# sprint_logger.net
KiCad netlist of a schematic drawn in EAGLE
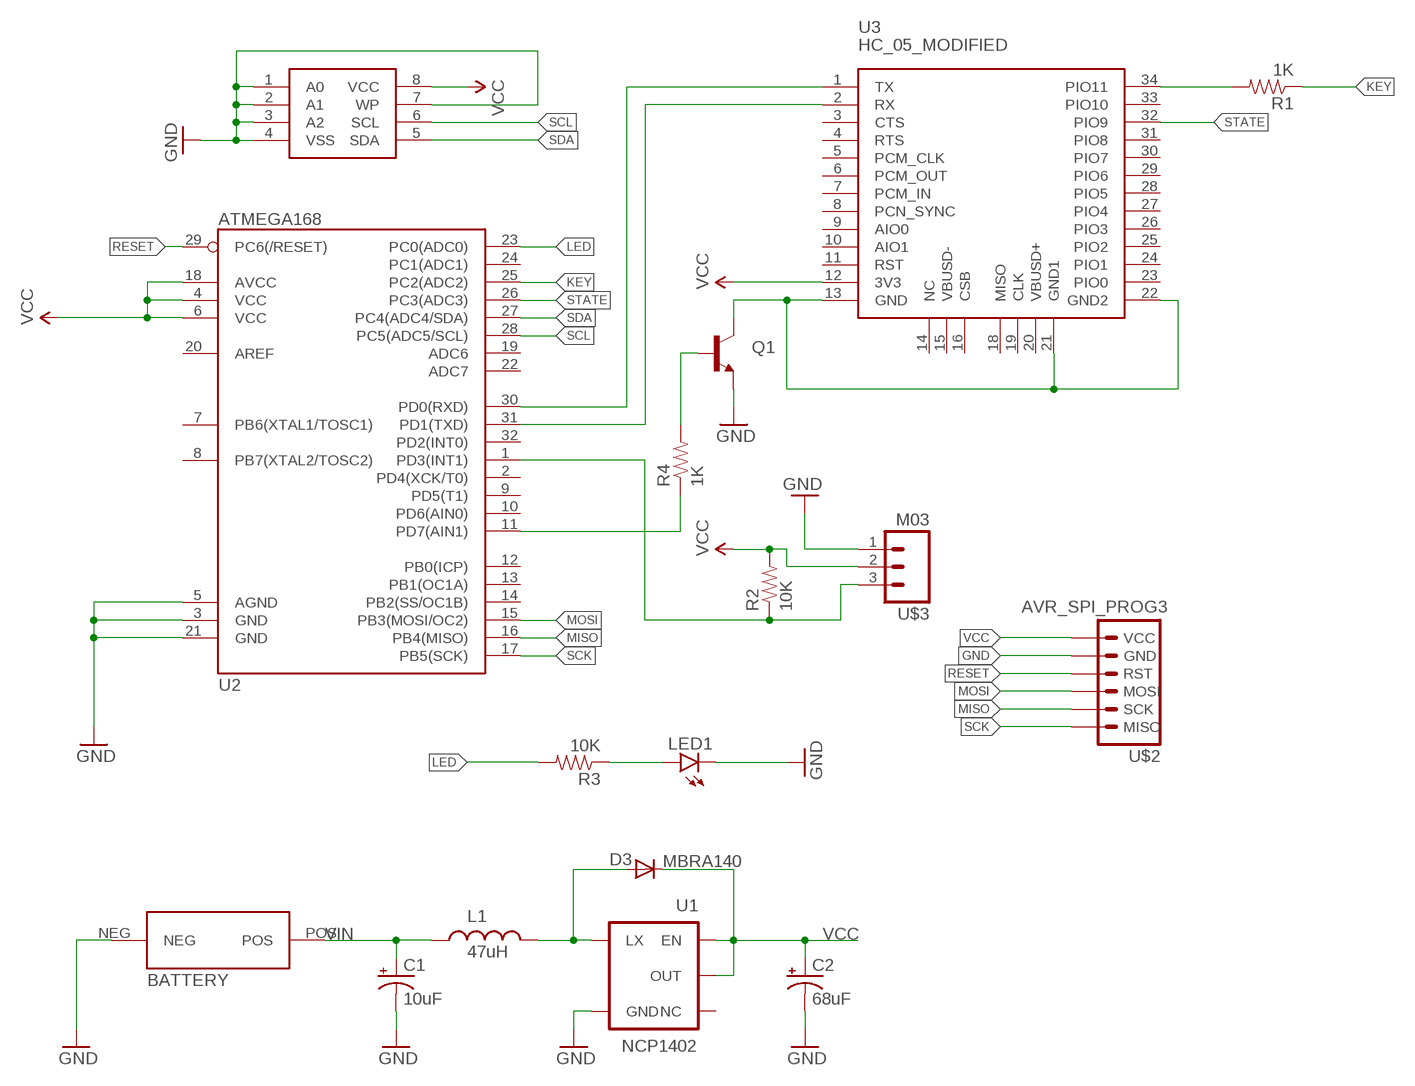
[diagram p0: schematic, sheet 1]

(export (version "E")
  (design (tool "Eeschema 10.0.6"))
  (components
    (comp (ref "BATTERY")
      (value "BATHOLDER-N-2470")
      (footprint "eagle-import:BATHOLDER-N-2470")
      (libsource (lib "eagle-import") (part "BATHOLDER-N-2470"))
    )
    (comp (ref "C1")
      (value "10uF")
      (footprint "eagle-import:EIA3216")
      (libsource (lib "eagle-import") (part "CAP_POL1206"))
    )
    (comp (ref "C2")
      (value "68uF")
      (footprint "eagle-import:EIA3528")
      (libsource (lib "eagle-import") (part "CAP_POL3528"))
    )
    (comp (ref "D3")
      (value "MBRA140")
      (footprint "eagle-import:SMA-DIODE")
      (libsource (lib "eagle-import") (part "DIODESMA"))
    )
    (comp (ref "L1")
      (value "47uH")
      (footprint "eagle-import:CR54")
      (libsource (lib "eagle-import") (part "INDUCTORCR54"))
    )
    (comp (ref "LED1")
      (value "LED1206")
      (footprint "eagle-import:LED-1206")
      (libsource (lib "eagle-import") (part "LED1206"))
    )
    (comp (ref "Q1")
      (value "TRANSISTOR_NPNSOT23")
      (footprint "eagle-import:SOT23")
      (libsource (lib "eagle-import") (part "TRANSISTOR_NPNSOT23"))
    )
    (comp (ref "R1")
      (value "1K")
      (footprint "eagle-import:0805")
      (libsource (lib "eagle-import") (part "RESISTOR0805-RES"))
    )
    (comp (ref "R2")
      (value "10K")
      (footprint "eagle-import:0805")
      (libsource (lib "eagle-import") (part "RESISTOR0805-RES"))
    )
    (comp (ref "R3")
      (value "10K")
      (footprint "eagle-import:0805")
      (libsource (lib "eagle-import") (part "RESISTOR0805-RES"))
    )
    (comp (ref "R4")
      (value "1K")
      (footprint "eagle-import:0805")
      (libsource (lib "eagle-import") (part "RESISTOR0805-RES"))
    )
    (comp (ref "U$1")
      (value "24AAXXX")
      (footprint "eagle-import:SOIC-8-EIAJ")
      (libsource (lib "eagle-import") (part "24AAXXX"))
    )
    (comp (ref "U$2")
      (value "AVR_SPI_PROG3")
      (footprint "eagle-import:1X06-SMD_EDGE")
      (libsource (lib "eagle-import") (part "AVR_SPI_PROG3"))
    )
    (comp (ref "U$3")
      (value "M03")
      (footprint "eagle-import:1X06-SMD_EDGE")
      (libsource (lib "eagle-import") (part "M03"))
    )
    (comp (ref "U1")
      (value "NCP1402")
      (footprint "eagle-import:SOT23-5")
      (libsource (lib "eagle-import") (part "V_REG_NCP1400SOT23-5"))
    )
    (comp (ref "U2")
      (value "ATMEGA168")
      (footprint "eagle-import:TQFP32-08")
      (libsource (lib "eagle-import") (part "ATMEGA168"))
    )
    (comp (ref "U3")
      (value "HC_05_MODIFIED")
      (footprint "eagle-import:BLUETOOTH_SMD_MODIFIED")
      (libsource (lib "eagle-import") (part "HC_05_MODIFIED"))
    )
  )
  (nets
    (net (code "1") (name "/VIN") (class "Default")
      (node (ref "BATTERY") (pin "POS") (pinfunction "POS_POS") (pintype "bidirectional"))
      (node (ref "C1") (pin "A") (pinfunction "+_A") (pintype "passive"))
      (node (ref "L1") (pin "P$1") (pinfunction "1_P$1") (pintype "passive"))
    )
    (net (code "2") (name "GND") (class "Default")
      (node (ref "BATTERY") (pin "NEG") (pinfunction "NEG_NEG") (pintype "bidirectional"))
      (node (ref "C1") (pin "C") (pinfunction "-_C") (pintype "passive"))
      (node (ref "C2") (pin "C") (pinfunction "-_C") (pintype "passive"))
      (node (ref "LED1") (pin "C") (pinfunction "C_C") (pintype "passive"))
      (node (ref "Q1") (pin "2") (pinfunction "E_2") (pintype "passive"))
      (node (ref "U$1") (pin "1") (pinfunction "A0_1") (pintype "bidirectional"))
      (node (ref "U$1") (pin "2") (pinfunction "A1_2") (pintype "bidirectional"))
      (node (ref "U$1") (pin "3") (pinfunction "A2_3") (pintype "bidirectional"))
      (node (ref "U$1") (pin "4") (pinfunction "VSS_4") (pintype "bidirectional"))
      (node (ref "U$1") (pin "7") (pinfunction "WP_7") (pintype "bidirectional"))
      (node (ref "U$2") (pin "2") (pinfunction "GND_2") (pintype "passive"))
      (node (ref "U$3") (pin "1") (pinfunction "1_1") (pintype "passive"))
      (node (ref "U1") (pin "4") (pinfunction "GND_4") (pintype "input"))
      (node (ref "U2") (pin "21") (pinfunction "GND_21") (pintype "bidirectional"))
      (node (ref "U2") (pin "3") (pinfunction "GND_3") (pintype "bidirectional"))
      (node (ref "U2") (pin "5") (pinfunction "AGND_5") (pintype "bidirectional"))
    )
    (net (code "3") (name "KEY") (class "Default")
      (node (ref "R1") (pin "1") (pinfunction "1_1") (pintype "passive"))
      (node (ref "U2") (pin "25") (pinfunction "PC2(ADC2)_25") (pintype "bidirectional"))
    )
    (net (code "4") (name "LED") (class "Default")
      (node (ref "R3") (pin "2") (pinfunction "2_2") (pintype "passive"))
      (node (ref "U2") (pin "23") (pinfunction "PC0(ADC0)_23") (pintype "bidirectional"))
    )
    (net (code "5") (name "MISO") (class "Default")
      (node (ref "U$2") (pin "5") (pinfunction "SCK_5") (pintype "passive"))
      (node (ref "U2") (pin "16") (pinfunction "PB4(MISO)_16") (pintype "bidirectional"))
    )
    (net (code "6") (name "MOSI") (class "Default")
      (node (ref "U$2") (pin "4") (pinfunction "MOSI_4") (pintype "passive"))
      (node (ref "U2") (pin "15") (pinfunction "PB3(MOSI/OC2)_15") (pintype "bidirectional"))
    )
    (net (code "7") (name "Net-(L1-2)") (class "Default")
      (node (ref "D3") (pin "A") (pinfunction "A_A") (pintype "passive"))
      (node (ref "L1") (pin "P$2") (pinfunction "2_P$2") (pintype "passive"))
      (node (ref "U1") (pin "5") (pinfunction "LX_5") (pintype "input"))
    )
    (net (code "8") (name "Net-(LED1-PadA)") (class "Default")
      (node (ref "LED1") (pin "A") (pinfunction "A_A") (pintype "passive"))
      (node (ref "R3") (pin "1") (pinfunction "1_1") (pintype "passive"))
    )
    (net (code "9") (name "Net-(Q1-B)") (class "Default")
      (node (ref "Q1") (pin "1") (pinfunction "B_1") (pintype "passive"))
      (node (ref "R4") (pin "2") (pinfunction "2_2") (pintype "passive"))
    )
    (net (code "10") (name "Net-(Q1-C)") (class "Default")
      (node (ref "Q1") (pin "3") (pinfunction "C_3") (pintype "passive"))
      (node (ref "U3") (pin "13") (pinfunction "GND_13") (pintype "bidirectional"))
      (node (ref "U3") (pin "21") (pinfunction "GND1_21") (pintype "bidirectional"))
      (node (ref "U3") (pin "22") (pinfunction "GND2_22") (pintype "bidirectional"))
    )
    (net (code "11") (name "Net-(U2-PD0(RXD))") (class "Default")
      (node (ref "U2") (pin "30") (pinfunction "PD0(RXD)_30") (pintype "bidirectional"))
      (node (ref "U3") (pin "1") (pinfunction "TX_1") (pintype "bidirectional"))
    )
    (net (code "12") (name "Net-(U2-PD1(TXD))") (class "Default")
      (node (ref "U2") (pin "31") (pinfunction "PD1(TXD)_31") (pintype "bidirectional"))
      (node (ref "U3") (pin "2") (pinfunction "RX_2") (pintype "bidirectional"))
    )
    (net (code "13") (name "Net-(U2-PD3(INT1))") (class "Default")
      (node (ref "R2") (pin "1") (pinfunction "1_1") (pintype "passive"))
      (node (ref "U$3") (pin "3") (pinfunction "3_3") (pintype "passive"))
      (node (ref "U2") (pin "1") (pinfunction "PD3(INT1)_1") (pintype "bidirectional"))
    )
    (net (code "14") (name "Net-(U2-PD7(AIN1))") (class "Default")
      (node (ref "R4") (pin "1") (pinfunction "1_1") (pintype "passive"))
      (node (ref "U2") (pin "11") (pinfunction "PD7(AIN1)_11") (pintype "bidirectional"))
    )
    (net (code "15") (name "Net-(U3-PIO11)") (class "Default")
      (node (ref "R1") (pin "2") (pinfunction "2_2") (pintype "passive"))
      (node (ref "U3") (pin "34") (pinfunction "PIO11_34") (pintype "bidirectional"))
    )
    (net (code "16") (name "RESET") (class "Default")
      (node (ref "U$2") (pin "3") (pinfunction "RST_3") (pintype "passive"))
      (node (ref "U2") (pin "29") (pinfunction "PC6(/RESET)_29") (pintype "bidirectional"))
    )
    (net (code "17") (name "SCK") (class "Default")
      (node (ref "U$2") (pin "6") (pinfunction "MISO_6") (pintype "passive"))
      (node (ref "U2") (pin "17") (pinfunction "PB5(SCK)_17") (pintype "bidirectional"))
    )
    (net (code "18") (name "SCL") (class "Default")
      (node (ref "U$1") (pin "6") (pinfunction "SCL_6") (pintype "bidirectional"))
      (node (ref "U2") (pin "28") (pinfunction "PC5(ADC5/SCL)_28") (pintype "bidirectional"))
    )
    (net (code "19") (name "SDA") (class "Default")
      (node (ref "U$1") (pin "5") (pinfunction "SDA_5") (pintype "bidirectional"))
      (node (ref "U2") (pin "27") (pinfunction "PC4(ADC4/SDA)_27") (pintype "bidirectional"))
    )
    (net (code "20") (name "STATE") (class "Default")
      (node (ref "U2") (pin "26") (pinfunction "PC3(ADC3)_26") (pintype "bidirectional"))
      (node (ref "U3") (pin "32") (pinfunction "PIO9_32") (pintype "bidirectional"))
    )
    (net (code "21") (name "VCC") (class "Default")
      (node (ref "C2") (pin "A") (pinfunction "+_A") (pintype "passive"))
      (node (ref "D3") (pin "C") (pinfunction "C_C") (pintype "passive"))
      (node (ref "R2") (pin "2") (pinfunction "2_2") (pintype "passive"))
      (node (ref "U$1") (pin "8") (pinfunction "VCC_8") (pintype "bidirectional"))
      (node (ref "U$2") (pin "1") (pinfunction "VCC_1") (pintype "passive"))
      (node (ref "U$3") (pin "2") (pinfunction "2_2") (pintype "passive"))
      (node (ref "U1") (pin "1") (pinfunction "EN_1") (pintype "input"))
      (node (ref "U1") (pin "2") (pinfunction "OUT_2") (pintype "passive"))
      (node (ref "U2") (pin "18") (pinfunction "AVCC_18") (pintype "bidirectional"))
      (node (ref "U2") (pin "4") (pinfunction "VCC_4") (pintype "bidirectional"))
      (node (ref "U2") (pin "6") (pinfunction "VCC_6") (pintype "bidirectional"))
      (node (ref "U3") (pin "12") (pinfunction "3V3_12") (pintype "bidirectional"))
    )
    (net (code "22") (name "unconnected-(U1-NC-Pad3)") (class "Default")
      (node (ref "U1") (pin "3") (pinfunction "NC_3") (pintype "input"))
    )
    (net (code "23") (name "unconnected-(U2-ADC6-Pad19)") (class "Default")
      (node (ref "U2") (pin "19") (pinfunction "ADC6_19") (pintype "bidirectional"))
    )
    (net (code "24") (name "unconnected-(U2-ADC7-Pad22)") (class "Default")
      (node (ref "U2") (pin "22") (pinfunction "ADC7_22") (pintype "bidirectional"))
    )
    (net (code "25") (name "unconnected-(U2-AREF-Pad20)") (class "Default")
      (node (ref "U2") (pin "20") (pinfunction "AREF_20") (pintype "bidirectional"))
    )
    (net (code "26") (name "unconnected-(U2-PB0(ICP)-Pad12)") (class "Default")
      (node (ref "U2") (pin "12") (pinfunction "PB0(ICP)_12") (pintype "bidirectional"))
    )
    (net (code "27") (name "unconnected-(U2-PB1(OC1A)-Pad13)") (class "Default")
      (node (ref "U2") (pin "13") (pinfunction "PB1(OC1A)_13") (pintype "bidirectional"))
    )
    (net (code "28") (name "unconnected-(U2-PB2(SS{slash}OC1B)-Pad14)") (class "Default")
      (node (ref "U2") (pin "14") (pinfunction "PB2(SS/OC1B)_14") (pintype "bidirectional"))
    )
    (net (code "29") (name "unconnected-(U2-PB6(XTAL1{slash}TOSC1)-Pad7)") (class "Default")
      (node (ref "U2") (pin "7") (pinfunction "PB6(XTAL1/TOSC1)_7") (pintype "bidirectional"))
    )
    (net (code "30") (name "unconnected-(U2-PB7(XTAL2{slash}TOSC2)-Pad8)") (class "Default")
      (node (ref "U2") (pin "8") (pinfunction "PB7(XTAL2/TOSC2)_8") (pintype "bidirectional"))
    )
    (net (code "31") (name "unconnected-(U2-PC1(ADC1)-Pad24)") (class "Default")
      (node (ref "U2") (pin "24") (pinfunction "PC1(ADC1)_24") (pintype "bidirectional"))
    )
    (net (code "32") (name "unconnected-(U2-PD2(INT0)-Pad32)") (class "Default")
      (node (ref "U2") (pin "32") (pinfunction "PD2(INT0)_32") (pintype "bidirectional"))
    )
    (net (code "33") (name "unconnected-(U2-PD4(XCK{slash}T0)-Pad2)") (class "Default")
      (node (ref "U2") (pin "2") (pinfunction "PD4(XCK/T0)_2") (pintype "bidirectional"))
    )
    (net (code "34") (name "unconnected-(U2-PD5(T1)-Pad9)") (class "Default")
      (node (ref "U2") (pin "9") (pinfunction "PD5(T1)_9") (pintype "bidirectional"))
    )
    (net (code "35") (name "unconnected-(U2-PD6(AIN0)-Pad10)") (class "Default")
      (node (ref "U2") (pin "10") (pinfunction "PD6(AIN0)_10") (pintype "bidirectional"))
    )
    (net (code "36") (name "unconnected-(U3-AIO0-Pad9)") (class "Default")
      (node (ref "U3") (pin "9") (pinfunction "AIO0_9") (pintype "bidirectional"))
    )
    (net (code "37") (name "unconnected-(U3-AIO1-Pad10)") (class "Default")
      (node (ref "U3") (pin "10") (pinfunction "AIO1_10") (pintype "bidirectional"))
    )
    (net (code "38") (name "unconnected-(U3-CLK-Pad19)") (class "Default")
      (node (ref "U3") (pin "19") (pinfunction "CLK_19") (pintype "bidirectional"))
    )
    (net (code "39") (name "unconnected-(U3-CSB-Pad16)") (class "Default")
      (node (ref "U3") (pin "16") (pinfunction "CSB_16") (pintype "bidirectional"))
    )
    (net (code "40") (name "unconnected-(U3-CTS-Pad3)") (class "Default")
      (node (ref "U3") (pin "3") (pinfunction "CTS_3") (pintype "bidirectional"))
    )
    (net (code "41") (name "unconnected-(U3-MISO-Pad18)") (class "Default")
      (node (ref "U3") (pin "18") (pinfunction "MISO_18") (pintype "bidirectional"))
    )
    (net (code "42") (name "unconnected-(U3-NC-Pad14)") (class "Default")
      (node (ref "U3") (pin "14") (pinfunction "NC_14") (pintype "bidirectional"))
    )
    (net (code "43") (name "unconnected-(U3-PCM_CLK-Pad5)") (class "Default")
      (node (ref "U3") (pin "5") (pinfunction "PCM_CLK_5") (pintype "bidirectional"))
    )
    (net (code "44") (name "unconnected-(U3-PCM_IN-Pad7)") (class "Default")
      (node (ref "U3") (pin "7") (pinfunction "PCM_IN_7") (pintype "bidirectional"))
    )
    (net (code "45") (name "unconnected-(U3-PCM_OUT-Pad6)") (class "Default")
      (node (ref "U3") (pin "6") (pinfunction "PCM_OUT_6") (pintype "bidirectional"))
    )
    (net (code "46") (name "unconnected-(U3-PCN_SYNC-Pad8)") (class "Default")
      (node (ref "U3") (pin "8") (pinfunction "PCN_SYNC_8") (pintype "bidirectional"))
    )
    (net (code "47") (name "unconnected-(U3-PIO0-Pad23)") (class "Default")
      (node (ref "U3") (pin "23") (pinfunction "PIO0_23") (pintype "bidirectional"))
    )
    (net (code "48") (name "unconnected-(U3-PIO1-Pad24)") (class "Default")
      (node (ref "U3") (pin "24") (pinfunction "PIO1_24") (pintype "bidirectional"))
    )
    (net (code "49") (name "unconnected-(U3-PIO2-Pad25)") (class "Default")
      (node (ref "U3") (pin "25") (pinfunction "PIO2_25") (pintype "bidirectional"))
    )
    (net (code "50") (name "unconnected-(U3-PIO3-Pad26)") (class "Default")
      (node (ref "U3") (pin "26") (pinfunction "PIO3_26") (pintype "bidirectional"))
    )
    (net (code "51") (name "unconnected-(U3-PIO4-Pad27)") (class "Default")
      (node (ref "U3") (pin "27") (pinfunction "PIO4_27") (pintype "bidirectional"))
    )
    (net (code "52") (name "unconnected-(U3-PIO5-Pad28)") (class "Default")
      (node (ref "U3") (pin "28") (pinfunction "PIO5_28") (pintype "bidirectional"))
    )
    (net (code "53") (name "unconnected-(U3-PIO6-Pad29)") (class "Default")
      (node (ref "U3") (pin "29") (pinfunction "PIO6_29") (pintype "bidirectional"))
    )
    (net (code "54") (name "unconnected-(U3-PIO7-Pad30)") (class "Default")
      (node (ref "U3") (pin "30") (pinfunction "PIO7_30") (pintype "bidirectional"))
    )
    (net (code "55") (name "unconnected-(U3-PIO8-Pad31)") (class "Default")
      (node (ref "U3") (pin "31") (pinfunction "PIO8_31") (pintype "bidirectional"))
    )
    (net (code "56") (name "unconnected-(U3-PIO10-Pad33)") (class "Default")
      (node (ref "U3") (pin "33") (pinfunction "PIO10_33") (pintype "bidirectional"))
    )
    (net (code "57") (name "unconnected-(U3-RST-Pad11)") (class "Default")
      (node (ref "U3") (pin "11") (pinfunction "RST_11") (pintype "bidirectional"))
    )
    (net (code "58") (name "unconnected-(U3-RTS-Pad4)") (class "Default")
      (node (ref "U3") (pin "4") (pinfunction "RTS_4") (pintype "bidirectional"))
    )
    (net (code "59") (name "unconnected-(U3-VBUSD+-Pad20)") (class "Default")
      (node (ref "U3") (pin "20") (pinfunction "VBUSD+_20") (pintype "bidirectional"))
    )
    (net (code "60") (name "unconnected-(U3-VBUSD--Pad15)") (class "Default")
      (node (ref "U3") (pin "15") (pinfunction "VBUSD-_15") (pintype "bidirectional"))
    )
  )
)
